# RS232_and_USB_ports.net
KiCad netlist of a schematic drawn in Altium Designer
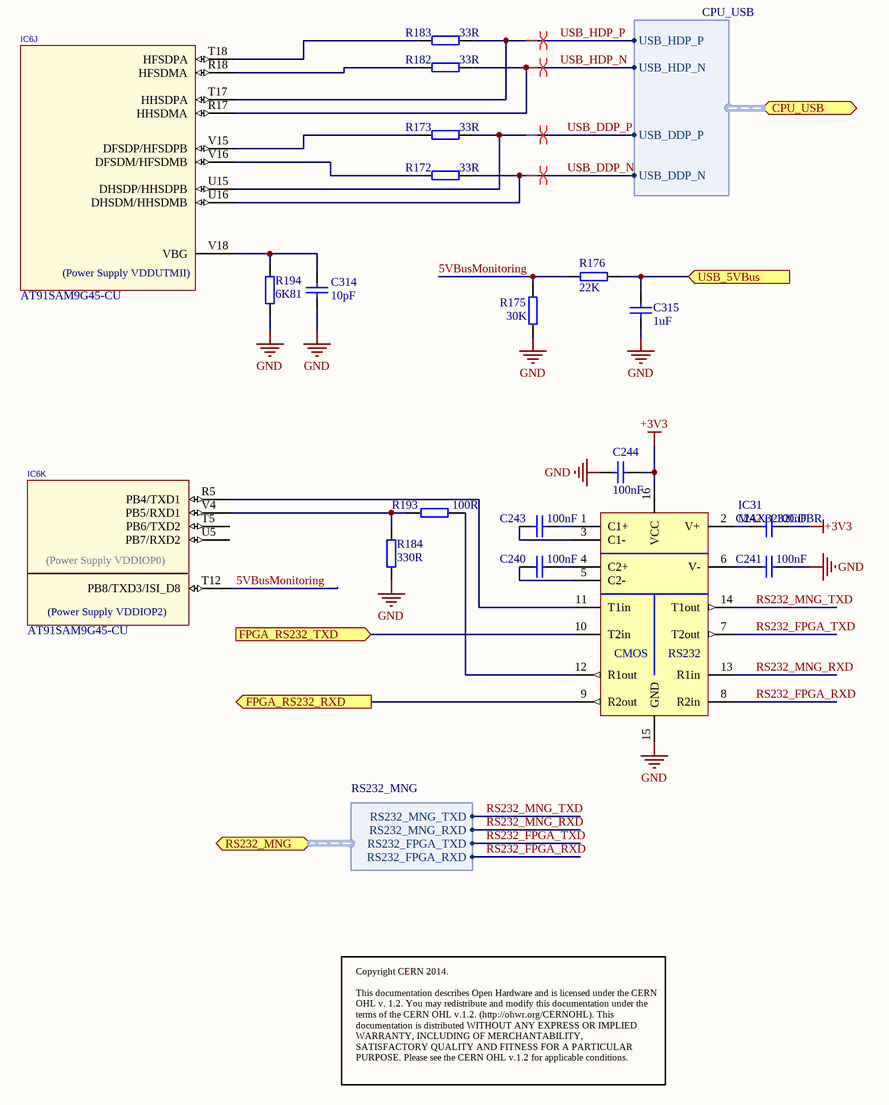
[diagram p0: RS232_and_USB_ports.SchDoc]

(export (version "E")
  (design (tool "Eeschema 10.0.6"))
  (components
    (comp (ref "C240")
      (value "100nF")
      (footprint "CC1005-0402")
      (description "Capacitor")
      (fields
        (field (name "TOLERANCE") "±10%")
        (field (name "VOLTAGE") "16V")
        (field (name "PUBLISHER") "Altium Limited")
      )
      (libsource (lib "wr_switch") (part "Cap"))
    )
    (comp (ref "C241")
      (value "100nF")
      (footprint "CC1005-0402")
      (description "Capacitor")
      (fields
        (field (name "TOLERANCE") "±10%")
        (field (name "VOLTAGE") "16V")
        (field (name "PUBLISHER") "Altium Limited")
      )
      (libsource (lib "wr_switch") (part "Cap"))
    )
    (comp (ref "C242")
      (value "100nF")
      (footprint "CC1005-0402")
      (description "Capacitor")
      (fields
        (field (name "TOLERANCE") "±10%")
        (field (name "VOLTAGE") "16V")
        (field (name "PUBLISHER") "Altium Limited")
      )
      (libsource (lib "wr_switch") (part "Cap"))
    )
    (comp (ref "C243")
      (value "100nF")
      (footprint "CC1005-0402")
      (description "Capacitor")
      (fields
        (field (name "TOLERANCE") "±10%")
        (field (name "VOLTAGE") "16V")
        (field (name "PUBLISHER") "Altium Limited")
      )
      (libsource (lib "wr_switch") (part "Cap"))
    )
    (comp (ref "C244")
      (value "100nF")
      (footprint "CC1005-0402")
      (description "Capacitor")
      (fields
        (field (name "TOLERANCE") "±10%")
        (field (name "VOLTAGE") "16V")
        (field (name "PUBLISHER") "Altium Limited")
      )
      (libsource (lib "wr_switch") (part "Cap"))
    )
    (comp (ref "C314")
      (value "10pF")
      (footprint "CC1005-0402")
      (description "Capacitor")
      (fields
        (field (name "TOLERANCE") "±10%")
        (field (name "VOLTAGE") "50V")
        (field (name "PUBLISHER") "Altium Limited")
      )
      (libsource (lib "wr_switch") (part "Cap"))
    )
    (comp (ref "C315")
      (value "1uF")
      (footprint "CC1005-0402")
      (description "Capacitor")
      (fields
        (field (name "TOLERANCE") "±10%")
        (field (name "VOLTAGE") "16V")
        (field (name "PUBLISHER") "Altium Limited")
      )
      (libsource (lib "wr_switch") (part "Cap"))
    )
    (comp (ref "IC6")
      (value "AT91SAM9G45-CU")
      (footprint "TFBGA324")
      (description "Atmel 400MHz ARM926 MCU")
      (libsource (lib "wr_switch") (part "AT91SAM9G45-CU"))
    )
    (comp (ref "IC31")
      (value "MAX3232CDBR")
      (footprint "SOP65P780X200-16N")
      (libsource (lib "wr_switch") (part "IFC_MAX3232"))
    )
    (comp (ref "R172")
      (value "33R")
      (footprint "0603")
      (description "SMD Resistor")
      (fields (field (name "TOLERANCE") "±1%"))
      (libsource (lib "wr_switch") (part "RES_SMD"))
    )
    (comp (ref "R173")
      (value "33R")
      (footprint "0603")
      (description "SMD Resistor")
      (fields (field (name "TOLERANCE") "±1%"))
      (libsource (lib "wr_switch") (part "RES_SMD"))
    )
    (comp (ref "R175")
      (value "30K")
      (footprint "0402")
      (description "SMD Resistor")
      (fields (field (name "TOLERANCE") "±1%"))
      (libsource (lib "wr_switch") (part "RES_SMD"))
    )
    (comp (ref "R176")
      (value "22K")
      (footprint "0402")
      (description "SMD Resistor")
      (fields (field (name "TOLERANCE") "±1%"))
      (libsource (lib "wr_switch") (part "RES_SMD"))
    )
    (comp (ref "R182")
      (value "33R")
      (footprint "0603")
      (description "SMD Resistor")
      (fields (field (name "TOLERANCE") "±1%"))
      (libsource (lib "wr_switch") (part "RES_SMD"))
    )
    (comp (ref "R183")
      (value "33R")
      (footprint "0603")
      (description "SMD Resistor")
      (fields (field (name "TOLERANCE") "±1%"))
      (libsource (lib "wr_switch") (part "RES_SMD"))
    )
    (comp (ref "R184")
      (value "330R")
      (footprint "0402")
      (description "SMD Resistor")
      (fields (field (name "TOLERANCE") "±1%"))
      (libsource (lib "wr_switch") (part "RES_SMD"))
    )
    (comp (ref "R193")
      (value "100R")
      (footprint "0402")
      (description "SMD Resistor")
      (fields (field (name "TOLERANCE") "±1%"))
      (libsource (lib "wr_switch") (part "RES_SMD"))
    )
    (comp (ref "R194")
      (value "6K81")
      (footprint "0402")
      (description "SMD Resistor")
      (fields (field (name "TOLERANCE") "±1%"))
      (libsource (lib "wr_switch") (part "RES_SMD"))
    )
  )
  (nets
    (net (code "3") (name "+3V3") (class "Default")
      (node (ref "C242") (pin "1") (pinfunction "1_1") (pintype "passive"))
      (node (ref "C244") (pin "1") (pinfunction "1_1") (pintype "passive"))
      (node (ref "IC31") (pin "16") (pinfunction "VCC_16") (pintype "power_in"))
    )
    (net (code "4") (name "/5VBusMonitoring") (class "Default")
      (node (ref "IC6") (pin "T12") (pinfunction "PB8/TXD3/ISI_D8_T12") (pintype "bidirectional"))
      (node (ref "R175") (pin "2") (pinfunction "2_2") (pintype "passive"))
      (node (ref "R176") (pin "2") (pinfunction "2_2") (pintype "passive"))
    )
    (net (code "5") (name "/FPGA_RS232_RXD") (class "Default")
      (node (ref "IC31") (pin "9") (pinfunction "R2out_9") (pintype "output"))
    )
    (net (code "6") (name "/FPGA_RS232_TXD") (class "Default")
      (node (ref "IC31") (pin "10") (pinfunction "T2in_10") (pintype "passive"))
    )
    (net (code "7") (name "/RS232_FPGA_RXD") (class "Default")
      (node (ref "IC31") (pin "8") (pinfunction "R2in_8") (pintype "passive"))
    )
    (net (code "8") (name "/RS232_FPGA_TXD") (class "Default")
      (node (ref "IC31") (pin "7") (pinfunction "T2out_7") (pintype "output"))
    )
    (net (code "9") (name "/RS232_MNG_RXD") (class "Default")
      (node (ref "IC31") (pin "13") (pinfunction "R1in_13") (pintype "passive"))
    )
    (net (code "10") (name "/RS232_MNG_TXD") (class "Default")
      (node (ref "IC31") (pin "14") (pinfunction "T1out_14") (pintype "output"))
    )
    (net (code "11") (name "/USB_5VBus") (class "Default")
      (node (ref "C315") (pin "1") (pinfunction "1_1") (pintype "passive"))
      (node (ref "R176") (pin "1") (pinfunction "1_1") (pintype "passive"))
    )
    (net (code "12") (name "/USB_DDP_N") (class "Default")
      (node (ref "IC6") (pin "U16") (pinfunction "DHSDM/HHSDMB_U16") (pintype "bidirectional"))
      (node (ref "R172") (pin "2") (pinfunction "2_2") (pintype "passive"))
    )
    (net (code "13") (name "/USB_DDP_P") (class "Default")
      (node (ref "IC6") (pin "U15") (pinfunction "DHSDP/HHSDPB_U15") (pintype "bidirectional"))
      (node (ref "R173") (pin "2") (pinfunction "2_2") (pintype "passive"))
    )
    (net (code "14") (name "/USB_HDP_N") (class "Default")
      (node (ref "IC6") (pin "R17") (pinfunction "HHSDMA_R17") (pintype "bidirectional"))
      (node (ref "R182") (pin "2") (pinfunction "2_2") (pintype "passive"))
    )
    (net (code "15") (name "/USB_HDP_P") (class "Default")
      (node (ref "IC6") (pin "T17") (pinfunction "HHSDPA_T17") (pintype "bidirectional"))
      (node (ref "R183") (pin "2") (pinfunction "2_2") (pintype "passive"))
    )
    (net (code "18") (name "GND") (class "Default")
      (node (ref "C241") (pin "1") (pinfunction "1_1") (pintype "passive"))
      (node (ref "C244") (pin "2") (pinfunction "2_2") (pintype "passive"))
      (node (ref "C314") (pin "1") (pinfunction "1_1") (pintype "passive"))
      (node (ref "C315") (pin "2") (pinfunction "2_2") (pintype "passive"))
      (node (ref "IC31") (pin "15") (pinfunction "GND_15") (pintype "power_in"))
      (node (ref "R175") (pin "1") (pinfunction "1_1") (pintype "passive"))
      (node (ref "R184") (pin "2") (pinfunction "2_2") (pintype "passive"))
      (node (ref "R194") (pin "1") (pinfunction "1_1") (pintype "passive"))
    )
    (net (code "19") (name "Net-(IC6J-DFSDM{slash}HFSDMB)") (class "Default")
      (node (ref "IC6") (pin "V16") (pinfunction "DFSDM/HFSDMB_V16") (pintype "bidirectional"))
      (node (ref "R172") (pin "1") (pinfunction "1_1") (pintype "passive"))
    )
    (net (code "20") (name "Net-(IC6J-DFSDP{slash}HFSDPB)") (class "Default")
      (node (ref "IC6") (pin "V15") (pinfunction "DFSDP/HFSDPB_V15") (pintype "bidirectional"))
      (node (ref "R173") (pin "1") (pinfunction "1_1") (pintype "passive"))
    )
    (net (code "21") (name "Net-(IC6J-HFSDMA)") (class "Default")
      (node (ref "IC6") (pin "R18") (pinfunction "HFSDMA_R18") (pintype "bidirectional"))
      (node (ref "R182") (pin "1") (pinfunction "1_1") (pintype "passive"))
    )
    (net (code "22") (name "Net-(IC6J-HFSDPA)") (class "Default")
      (node (ref "IC6") (pin "T18") (pinfunction "HFSDPA_T18") (pintype "bidirectional"))
      (node (ref "R183") (pin "1") (pinfunction "1_1") (pintype "passive"))
    )
    (net (code "23") (name "Net-(IC6J-VBG)") (class "Default")
      (node (ref "C314") (pin "2") (pinfunction "2_2") (pintype "passive"))
      (node (ref "IC6") (pin "V18") (pinfunction "VBG_V18") (pintype "passive"))
      (node (ref "R194") (pin "2") (pinfunction "2_2") (pintype "passive"))
    )
    (net (code "24") (name "Net-(IC6K-PB5{slash}RXD1)") (class "Default")
      (node (ref "IC6") (pin "V4") (pinfunction "PB5/RXD1_V4") (pintype "bidirectional"))
      (node (ref "R184") (pin "1") (pinfunction "1_1") (pintype "passive"))
      (node (ref "R193") (pin "2") (pinfunction "2_2") (pintype "passive"))
    )
    (net (code "25") (name "Net-(IC31-C1+)") (class "Default")
      (node (ref "C243") (pin "1") (pinfunction "1_1") (pintype "passive"))
      (node (ref "IC31") (pin "1") (pinfunction "C1+_1") (pintype "passive"))
    )
    (net (code "26") (name "Net-(IC31-C1-)") (class "Default")
      (node (ref "C243") (pin "2") (pinfunction "2_2") (pintype "passive"))
      (node (ref "IC31") (pin "3") (pinfunction "C1-_3") (pintype "passive"))
    )
    (net (code "27") (name "Net-(IC31-C2+)") (class "Default")
      (node (ref "C240") (pin "1") (pinfunction "1_1") (pintype "passive"))
      (node (ref "IC31") (pin "4") (pinfunction "C2+_4") (pintype "passive"))
    )
    (net (code "28") (name "Net-(IC31-C2-)") (class "Default")
      (node (ref "C240") (pin "2") (pinfunction "2_2") (pintype "passive"))
      (node (ref "IC31") (pin "5") (pinfunction "C2-_5") (pintype "passive"))
    )
    (net (code "29") (name "Net-(IC31-R1out)") (class "Default")
      (node (ref "IC31") (pin "12") (pinfunction "R1out_12") (pintype "output"))
      (node (ref "R193") (pin "1") (pinfunction "1_1") (pintype "passive"))
    )
    (net (code "30") (name "Net-(IC31-T1in)") (class "Default")
      (node (ref "IC31") (pin "11") (pinfunction "T1in_11") (pintype "passive"))
      (node (ref "IC6") (pin "R5") (pinfunction "PB4/TXD1_R5") (pintype "bidirectional"))
    )
    (net (code "31") (name "Net-(IC31-V+)") (class "Default")
      (node (ref "C242") (pin "2") (pinfunction "2_2") (pintype "passive"))
      (node (ref "IC31") (pin "2") (pinfunction "V+_2") (pintype "passive"))
    )
    (net (code "32") (name "Net-(IC31-V-)") (class "Default")
      (node (ref "C241") (pin "2") (pinfunction "2_2") (pintype "passive"))
      (node (ref "IC31") (pin "6") (pinfunction "V-_6") (pintype "passive"))
    )
    (net (code "33") (name "unconnected-(IC6K-PB6{slash}TXD2-PadT5)") (class "Default")
      (node (ref "IC6") (pin "T5") (pinfunction "PB6/TXD2_T5") (pintype "bidirectional"))
    )
    (net (code "34") (name "unconnected-(IC6K-PB7{slash}RXD2-PadU5)") (class "Default")
      (node (ref "IC6") (pin "U5") (pinfunction "PB7/RXD2_U5") (pintype "bidirectional"))
    )
  )
)
